# manual-switch.net
KiCad netlist of a schematic drawn in EAGLE
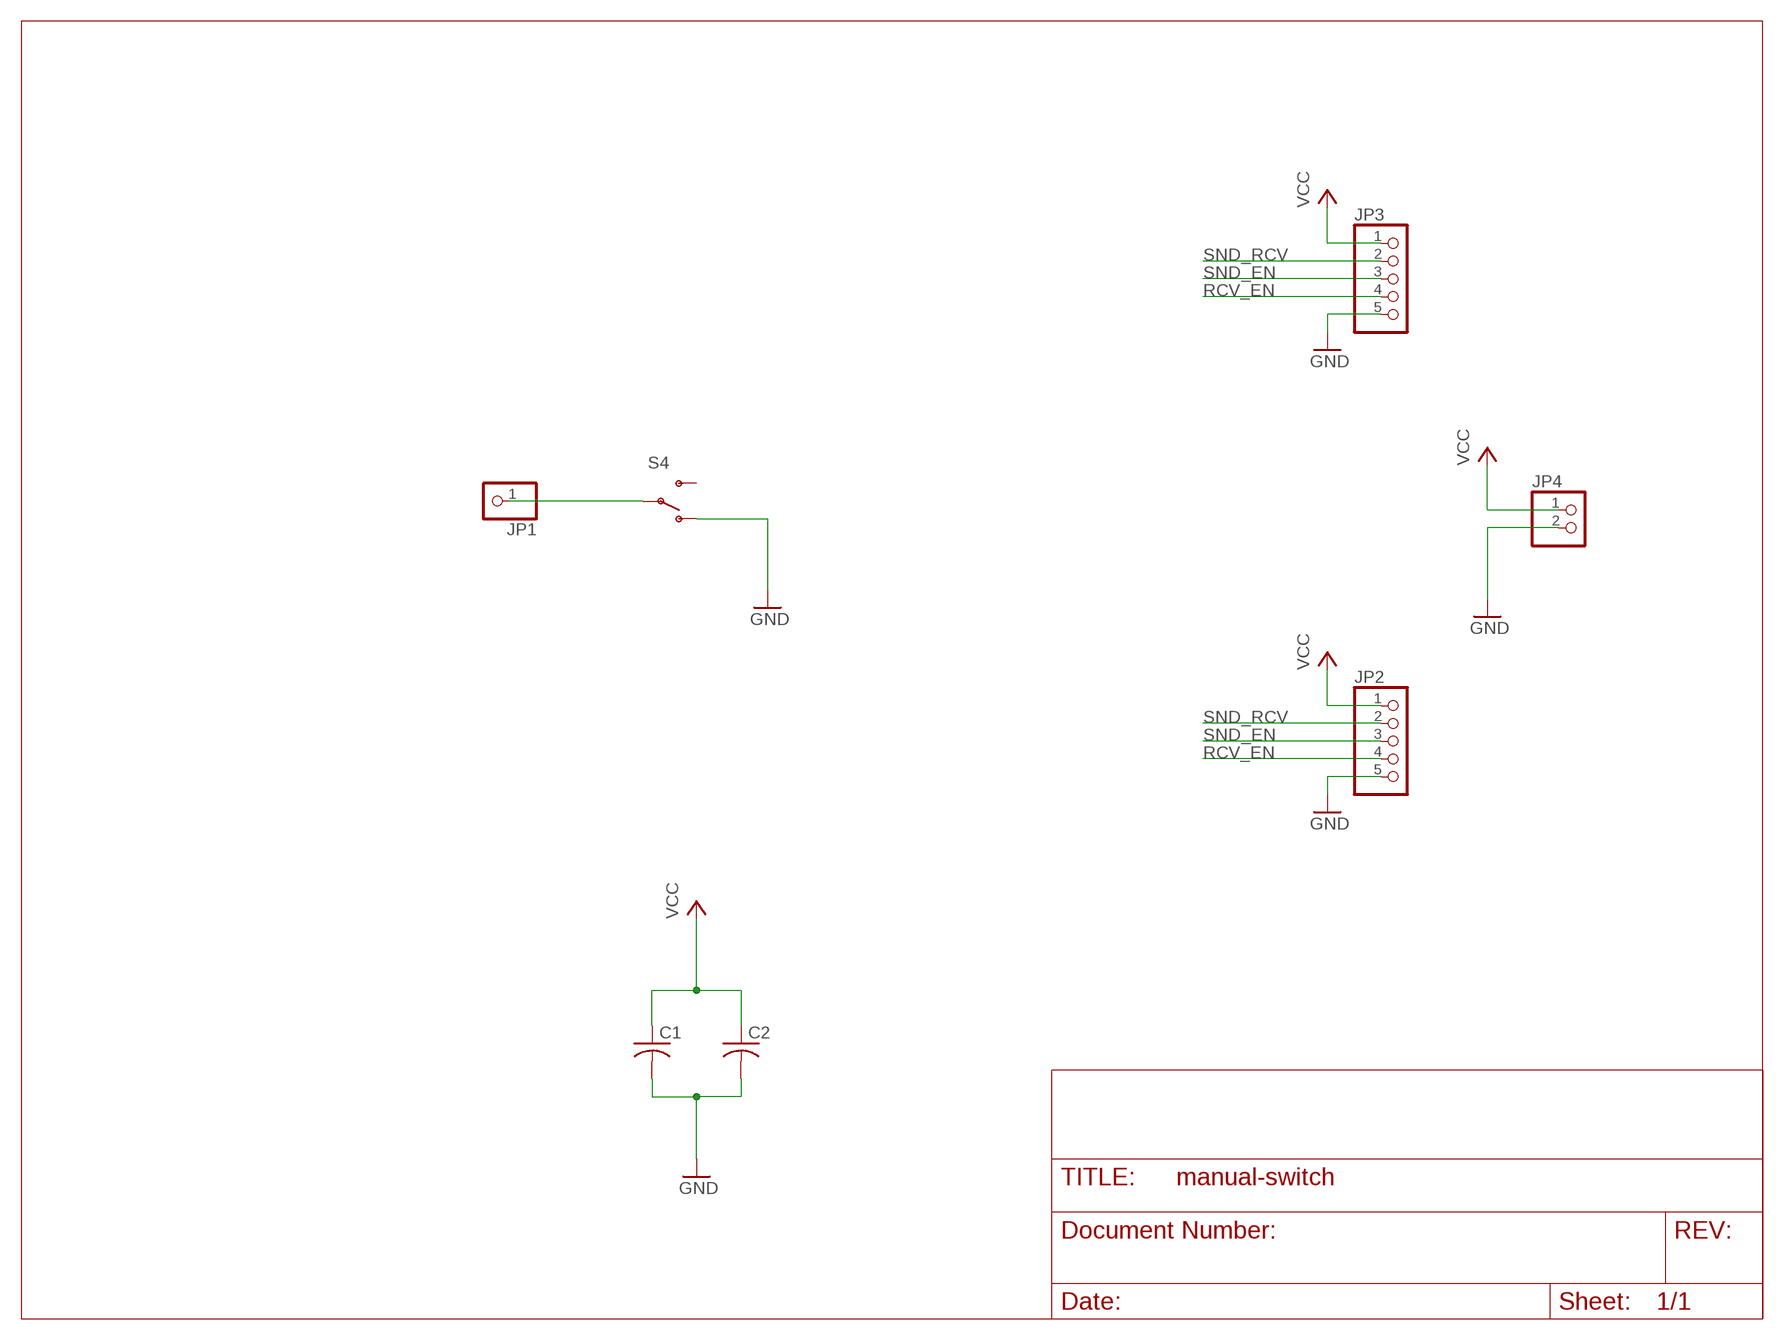
[diagram p0: schematic, sheet 1]

(export (version "E")
  (design (tool "Eeschema 10.0.6"))
  (components
    (comp (ref "C1")
      (value "C-USC0805")
      (footprint "eagle-import:C0805")
      (libsource (lib "eagle-import") (part "C-USC0805"))
    )
    (comp (ref "C2")
      (value "C-USC0805")
      (footprint "eagle-import:C0805")
      (libsource (lib "eagle-import") (part "C-USC0805"))
    )
    (comp (ref "JP1")
      (value "PINHD-1X1")
      (footprint "eagle-import:1X01")
      (libsource (lib "eagle-import") (part "PINHD-1X1"))
    )
    (comp (ref "JP2")
      (value "PINHD-1X5")
      (footprint "eagle-import:1X05")
      (libsource (lib "eagle-import") (part "PINHD-1X5"))
    )
    (comp (ref "JP3")
      (value "PINHD-1X5")
      (footprint "eagle-import:1X05")
      (libsource (lib "eagle-import") (part "PINHD-1X5"))
    )
    (comp (ref "JP4")
      (value "PINHD-1X2")
      (footprint "eagle-import:1X02")
      (libsource (lib "eagle-import") (part "PINHD-1X2"))
    )
    (comp (ref "S4")
      (value "SWITCH-SPDTPTH")
      (footprint "eagle-import:SWITCH-SPDT")
      (libsource (lib "eagle-import") (part "SWITCH-SPDTPTH"))
    )
  )
  (nets
    (net (code "1") (name "/RCV_EN") (class "Default")
      (node (ref "JP2") (pin "4") (pinfunction "4_4") (pintype "passive"))
      (node (ref "JP3") (pin "4") (pinfunction "4_4") (pintype "passive"))
    )
    (net (code "2") (name "/SND_EN") (class "Default")
      (node (ref "JP2") (pin "3") (pinfunction "3_3") (pintype "passive"))
      (node (ref "JP3") (pin "3") (pinfunction "3_3") (pintype "passive"))
    )
    (net (code "3") (name "/SND_RCV") (class "Default")
      (node (ref "JP2") (pin "2") (pinfunction "2_2") (pintype "passive"))
      (node (ref "JP3") (pin "2") (pinfunction "2_2") (pintype "passive"))
    )
    (net (code "4") (name "GND") (class "Default")
      (node (ref "C1") (pin "2") (pinfunction "2_2") (pintype "passive"))
      (node (ref "C2") (pin "2") (pinfunction "2_2") (pintype "passive"))
      (node (ref "JP2") (pin "5") (pinfunction "5_5") (pintype "passive"))
      (node (ref "JP3") (pin "5") (pinfunction "5_5") (pintype "passive"))
      (node (ref "JP4") (pin "2") (pinfunction "2_2") (pintype "passive"))
      (node (ref "S4") (pin "1") (pinfunction "O_1") (pintype "passive"))
    )
    (net (code "5") (name "Net-(S4-P)") (class "Default")
      (node (ref "JP1") (pin "1") (pinfunction "1_1") (pintype "passive"))
      (node (ref "S4") (pin "2") (pinfunction "P_2") (pintype "passive"))
    )
    (net (code "6") (name "VCC") (class "Default")
      (node (ref "C1") (pin "1") (pinfunction "1_1") (pintype "passive"))
      (node (ref "C2") (pin "1") (pinfunction "1_1") (pintype "passive"))
      (node (ref "JP2") (pin "1") (pinfunction "1_1") (pintype "passive"))
      (node (ref "JP3") (pin "1") (pinfunction "1_1") (pintype "passive"))
      (node (ref "JP4") (pin "1") (pinfunction "1_1") (pintype "passive"))
    )
    (net (code "7") (name "unconnected-(S4-S-Pad3)") (class "Default")
      (node (ref "S4") (pin "3") (pinfunction "S_3") (pintype "passive"))
    )
  )
)
